# schematic.net
KiCad netlist of a schematic drawn in EasyEDA
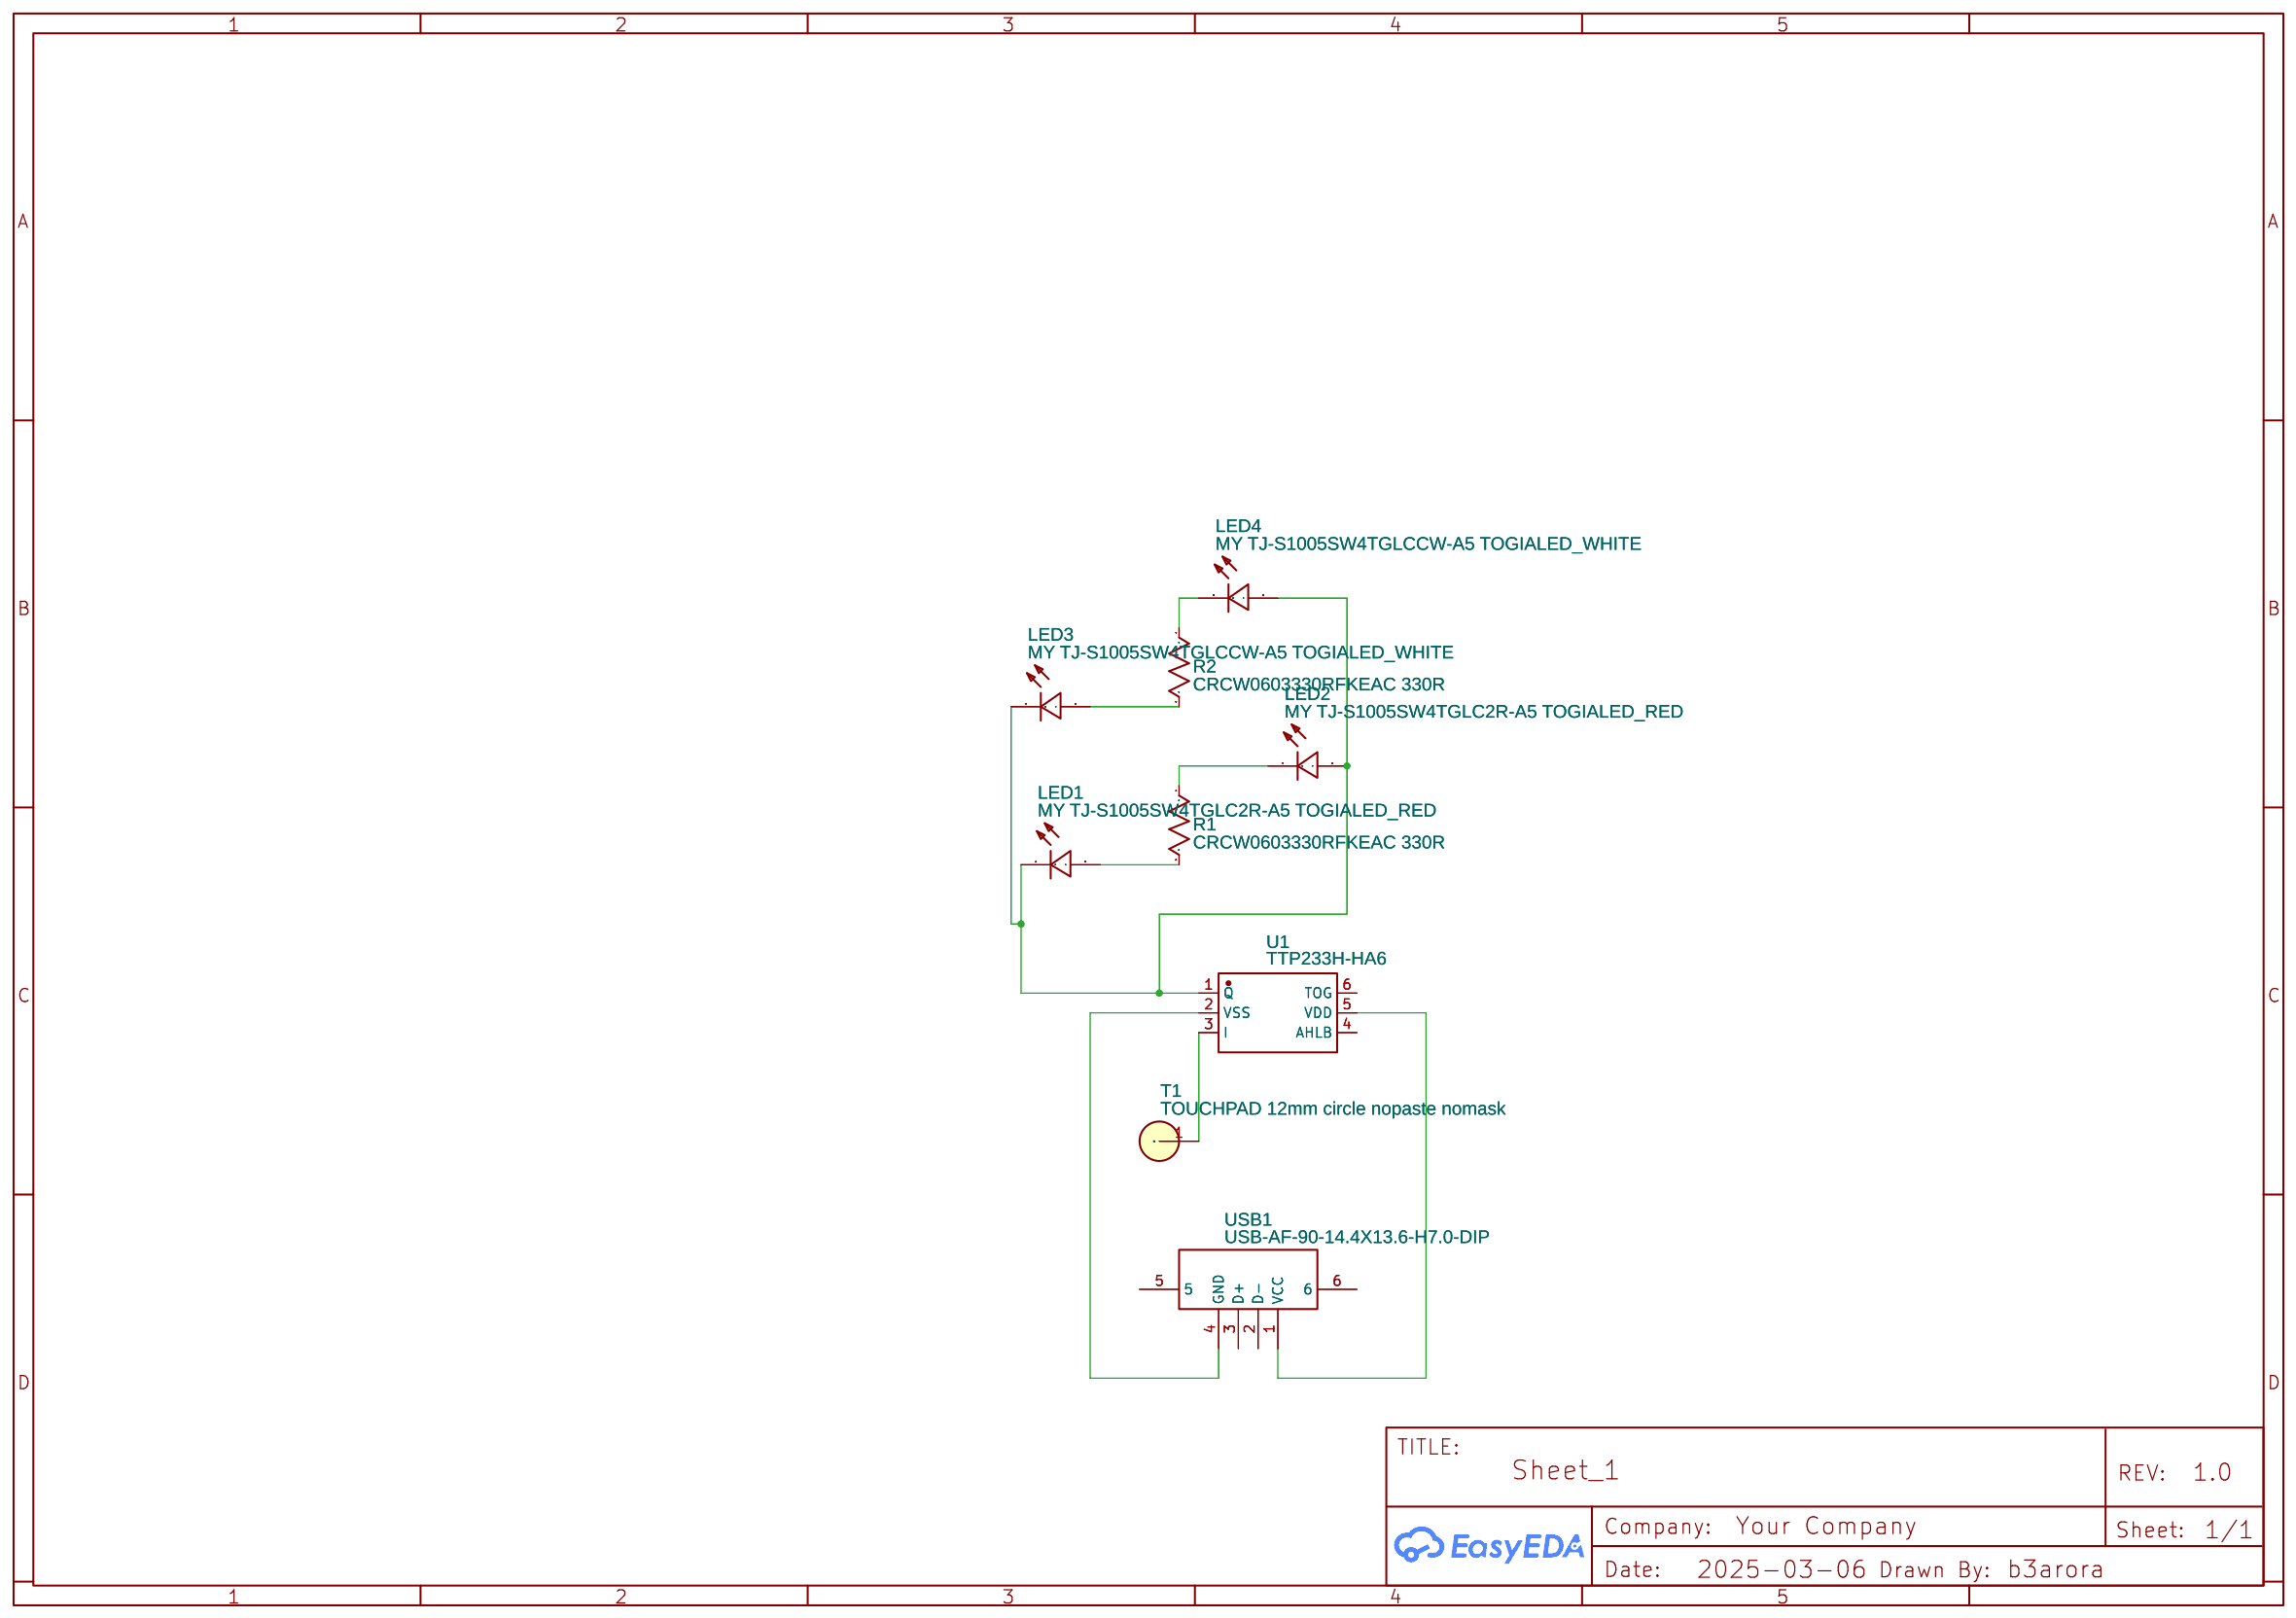
[diagram p0: schematic sheet]

(export (version "E")
  (design (tool "Eeschema 10.0.6"))
  (components
    (comp (ref "LED1")
      (value "MY TJ-S1005SW4TGLC2R-A5 TOGIALED_RED")
      (fields
        (field (name "Manufacturer Part") "TJ-S1005SW4TGLC2R-A5")
        (field (name "Manufacturer") "TOGIALED(统佳)")
      )
      (libsource (lib "") (part "MY TJ-S1005SW4TGLC2R-A5 TOGIALED_RED"))
    )
    (comp (ref "LED2")
      (value "MY TJ-S1005SW4TGLC2R-A5 TOGIALED_RED")
      (fields
        (field (name "Manufacturer Part") "TJ-S1005SW4TGLC2R-A5")
        (field (name "Manufacturer") "TOGIALED(统佳)")
      )
      (libsource (lib "") (part "MY TJ-S1005SW4TGLC2R-A5 TOGIALED_RED"))
    )
    (comp (ref "LED3")
      (value "MY TJ-S1005SW4TGLCCW-A5 TOGIALED_WHITE")
      (fields
        (field (name "Manufacturer Part") "TJ-S1005SW4TGLCCW-A5")
        (field (name "Manufacturer") "TOGIALED(统佳)")
      )
      (libsource (lib "") (part "MY TJ-S1005SW4TGLCCW-A5 TOGIALED_WHITE"))
    )
    (comp (ref "LED4")
      (value "MY TJ-S1005SW4TGLCCW-A5 TOGIALED_WHITE")
      (fields
        (field (name "Manufacturer Part") "TJ-S1005SW4TGLCCW-A5")
        (field (name "Manufacturer") "TOGIALED(统佳)")
      )
      (libsource (lib "") (part "MY TJ-S1005SW4TGLCCW-A5 TOGIALED_WHITE"))
    )
    (comp (ref "R1")
      (value "CRCW0603330RFKEAC 330R")
      (fields (field (name "Manufacturer Part") "CRCW0603330RFKEAC") (field (name "Manufacturer") "Vishay"))
      (libsource (lib "") (part "CRCW0603330RFKEAC 330R"))
    )
    (comp (ref "R2")
      (value "CRCW0603330RFKEAC 330R")
      (fields (field (name "Manufacturer Part") "CRCW0603330RFKEAC") (field (name "Manufacturer") "Vishay"))
      (libsource (lib "") (part "CRCW0603330RFKEAC 330R"))
    )
    (comp (ref "T1")
      (value "TOUCHPAD 12mm circle nopaste nomask")
      (libsource (lib "") (part "TOUCHPAD 12mm circle nopaste nomask"))
    )
    (comp (ref "U1")
      (value "TTP233H-HA6")
      (fields (field (name "Manufacturer") "TONTEK(通泰)"))
      (libsource (lib "") (part "TTP233H-HA6"))
    )
    (comp (ref "USB1")
      (value "USB-AF-90-14.4X13.6-H7.0-DIP")
      (fields (field (name "Manufacturer Part") "903-131A1011D10100") (field (name "Manufacturer") "精拓金"))
      (libsource (lib "") (part "USB-AF-90-14.4X13.6-H7.0-DIP"))
    )
  )
  (nets
    (net (code "1") (name "Net-(LED1-A)") (class "Default")
      (node (ref "LED1") (pin "2") (pinfunction "A_2") (pintype "unspecified"))
      (node (ref "R1") (pin "2") (pinfunction "2_2") (pintype "unspecified"))
    )
    (net (code "2") (name "Net-(LED1-C)") (class "Default")
      (node (ref "LED1") (pin "1") (pinfunction "C_1") (pintype "unspecified"))
      (node (ref "LED2") (pin "2") (pinfunction "A_2") (pintype "unspecified"))
      (node (ref "LED3") (pin "1") (pinfunction "C_1") (pintype "unspecified"))
      (node (ref "LED4") (pin "2") (pinfunction "A_2") (pintype "unspecified"))
      (node (ref "U1") (pin "1") (pinfunction "Q_1") (pintype "unspecified"))
    )
    (net (code "3") (name "Net-(LED2-C)") (class "Default")
      (node (ref "LED2") (pin "1") (pinfunction "C_1") (pintype "unspecified"))
      (node (ref "R1") (pin "1") (pinfunction "1_1") (pintype "unspecified"))
    )
    (net (code "4") (name "Net-(LED3-A)") (class "Default")
      (node (ref "LED3") (pin "2") (pinfunction "A_2") (pintype "unspecified"))
      (node (ref "R2") (pin "2") (pinfunction "2_2") (pintype "unspecified"))
    )
    (net (code "5") (name "Net-(LED4-C)") (class "Default")
      (node (ref "LED4") (pin "1") (pinfunction "C_1") (pintype "unspecified"))
      (node (ref "R2") (pin "1") (pinfunction "1_1") (pintype "unspecified"))
    )
    (net (code "6") (name "Net-(T1-Touch)") (class "Default")
      (node (ref "T1") (pin "1") (pinfunction "Touch_1") (pintype "unspecified"))
      (node (ref "U1") (pin "3") (pinfunction "I_3") (pintype "unspecified"))
    )
    (net (code "7") (name "Net-(U1-VDD)") (class "Default")
      (node (ref "U1") (pin "5") (pinfunction "VDD_5") (pintype "unspecified"))
      (node (ref "USB1") (pin "1") (pinfunction "VCC_1") (pintype "unspecified"))
    )
    (net (code "8") (name "Net-(U1-VSS)") (class "Default")
      (node (ref "U1") (pin "2") (pinfunction "VSS_2") (pintype "unspecified"))
      (node (ref "USB1") (pin "4") (pinfunction "GND_4") (pintype "unspecified"))
    )
    (net (code "9") (name "unconnected-(U1-AHLB-Pad4)") (class "Default")
      (node (ref "U1") (pin "4") (pinfunction "AHLB_4") (pintype "unspecified"))
    )
    (net (code "10") (name "unconnected-(U1-TOG-Pad6)") (class "Default")
      (node (ref "U1") (pin "6") (pinfunction "TOG_6") (pintype "unspecified"))
    )
    (net (code "11") (name "unconnected-(USB1-D+-Pad3)") (class "Default")
      (node (ref "USB1") (pin "3") (pinfunction "D+_3") (pintype "unspecified"))
    )
    (net (code "12") (name "unconnected-(USB1-D--Pad2)") (class "Default")
      (node (ref "USB1") (pin "2") (pinfunction "D-_2") (pintype "unspecified"))
    )
    (net (code "13") (name "unconnected-(USB1-Pad5)") (class "Default")
      (node (ref "USB1") (pin "5") (pinfunction "5_5") (pintype "unspecified"))
    )
    (net (code "14") (name "unconnected-(USB1-Pad6)") (class "Default")
      (node (ref "USB1") (pin "6") (pinfunction "6_6") (pintype "unspecified"))
    )
  )
)
